# TinySmps.net
KiCad netlist of a schematic drawn in EAGLE
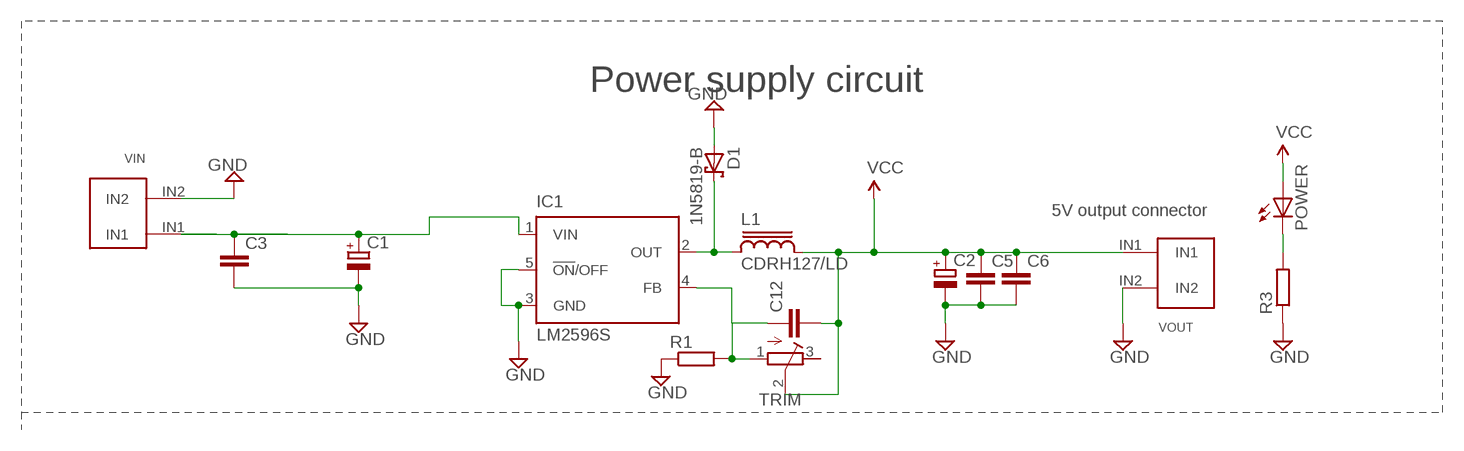
[diagram p0: schematic, sheet 1]

(export (version "E")
  (design (tool "Eeschema 10.0.6"))
  (components
    (comp (ref "C1")
      (value "CPOL-EUE5-10.5")
      (footprint "eagle-import:E5-10,5")
      (libsource (lib "eagle-import") (part "CPOL-EUE5-10.5"))
    )
    (comp (ref "C2")
      (value "CPOL-EUE5-10.5")
      (footprint "eagle-import:E5-10,5")
      (libsource (lib "eagle-import") (part "CPOL-EUE5-10.5"))
    )
    (comp (ref "C3")
      (value "C-EUC1206")
      (footprint "eagle-import:C1206")
      (libsource (lib "eagle-import") (part "C-EUC1206"))
    )
    (comp (ref "C5")
      (value "C-EUC1206")
      (footprint "eagle-import:C1206")
      (libsource (lib "eagle-import") (part "C-EUC1206"))
    )
    (comp (ref "C6")
      (value "C-EUC1206")
      (footprint "eagle-import:C1206")
      (libsource (lib "eagle-import") (part "C-EUC1206"))
    )
    (comp (ref "C12")
      (value "C2,5-3")
      (footprint "eagle-import:C2.5-3")
      (libsource (lib "eagle-import") (part "C2,5-3"))
    )
    (comp (ref "D1")
      (value "1N5819-B")
      (footprint "eagle-import:DO41-7.6")
      (libsource (lib "eagle-import") (part "1N5819-B"))
    )
    (comp (ref "IC1")
      (value "LM2596S")
      (footprint "eagle-import:TO263-5")
      (fields (field (name "MF") "NATIONAL SEMICONDUCTOR") (field (name "MPN") "LM2596S-ADJ/NOPB"))
      (libsource (lib "eagle-import") (part "LM2596S"))
    )
    (comp (ref "L1")
      (value "CDRH127/LD")
      (footprint "eagle-import:CDRH127_LD")
      (libsource (lib "eagle-import") (part "CDRH127/LD"))
    )
    (comp (ref "POWER")
      (value "LEDSML0805")
      (footprint "eagle-import:SML0805")
      (libsource (lib "eagle-import") (part "LEDSML0805"))
    )
    (comp (ref "R1")
      (value "R-EU_0204/7")
      (footprint "eagle-import:0204_7")
      (libsource (lib "eagle-import") (part "R-EU_0204/7"))
    )
    (comp (ref "R3")
      (value "R-EU_R1206")
      (footprint "eagle-import:R1206")
      (libsource (lib "eagle-import") (part "resistor_R-EU_R1206"))
    )
    (comp (ref "TRIM")
      (value "R-TRIMM3296W")
      (footprint "eagle-import:RTRIM3296W")
      (libsource (lib "eagle-import") (part "R-TRIMM3296W"))
    )
    (comp (ref "VIN")
      (value "1X2_5MM")
      (footprint "eagle-import:1X2_5MM")
      (libsource (lib "eagle-import") (part "1X2_5MM"))
    )
    (comp (ref "VOUT")
      (value "1X2_5MM")
      (footprint "eagle-import:1X2_5MM")
      (libsource (lib "eagle-import") (part "1X2_5MM"))
    )
  )
  (nets
    (net (code "1") (name "GND") (class "Default")
      (node (ref "C1") (pin "-") (pinfunction "-_-") (pintype "passive"))
      (node (ref "C2") (pin "-") (pinfunction "-_-") (pintype "passive"))
      (node (ref "C3") (pin "2") (pinfunction "2_2") (pintype "passive"))
      (node (ref "C5") (pin "2") (pinfunction "2_2") (pintype "passive"))
      (node (ref "C6") (pin "2") (pinfunction "2_2") (pintype "passive"))
      (node (ref "D1") (pin "A") (pinfunction "A_A") (pintype "passive"))
      (node (ref "IC1") (pin "3") (pinfunction "GND_3") (pintype "power_in"))
      (node (ref "IC1") (pin "5") (pinfunction "~{ON}/OFF_5") (pintype "input"))
      (node (ref "R1") (pin "1") (pinfunction "1_1") (pintype "passive"))
      (node (ref "R3") (pin "1") (pinfunction "1_1") (pintype "passive"))
      (node (ref "VIN") (pin "IN2") (pinfunction "IN2_IN2") (pintype "bidirectional"))
      (node (ref "VOUT") (pin "IN2") (pinfunction "IN2_IN2") (pintype "bidirectional"))
    )
    (net (code "2") (name "Net-(IC1-FB)") (class "Default")
      (node (ref "C12") (pin "1") (pinfunction "1_1") (pintype "passive"))
      (node (ref "IC1") (pin "4") (pinfunction "FB_4") (pintype "input"))
      (node (ref "R1") (pin "2") (pinfunction "2_2") (pintype "passive"))
      (node (ref "TRIM") (pin "1") (pinfunction "A_1") (pintype "passive"))
    )
    (net (code "3") (name "Net-(IC1-OUT)") (class "Default")
      (node (ref "D1") (pin "C") (pinfunction "C_C") (pintype "passive"))
      (node (ref "IC1") (pin "2") (pinfunction "OUT_2") (pintype "output"))
      (node (ref "L1") (pin "1") (pinfunction "1_1") (pintype "passive"))
    )
    (net (code "4") (name "Net-(IC1-VIN)") (class "Default")
      (node (ref "C1") (pin "+") (pinfunction "+_+") (pintype "passive"))
      (node (ref "C3") (pin "1") (pinfunction "1_1") (pintype "passive"))
      (node (ref "IC1") (pin "1") (pinfunction "VIN_1") (pintype "input"))
      (node (ref "VIN") (pin "IN1") (pinfunction "IN1_IN1") (pintype "bidirectional"))
    )
    (net (code "5") (name "Net-(POWER-PadC)") (class "Default")
      (node (ref "POWER") (pin "C") (pinfunction "C_C") (pintype "passive"))
      (node (ref "R3") (pin "2") (pinfunction "2_2") (pintype "passive"))
    )
    (net (code "6") (name "VCC") (class "Default")
      (node (ref "C12") (pin "2") (pinfunction "2_2") (pintype "passive"))
      (node (ref "C2") (pin "+") (pinfunction "+_+") (pintype "passive"))
      (node (ref "C5") (pin "1") (pinfunction "1_1") (pintype "passive"))
      (node (ref "C6") (pin "1") (pinfunction "1_1") (pintype "passive"))
      (node (ref "L1") (pin "2") (pinfunction "2_2") (pintype "passive"))
      (node (ref "POWER") (pin "A") (pinfunction "A_A") (pintype "passive"))
      (node (ref "TRIM") (pin "2") (pinfunction "S_2") (pintype "passive"))
      (node (ref "VOUT") (pin "IN1") (pinfunction "IN1_IN1") (pintype "bidirectional"))
    )
    (net (code "7") (name "unconnected-(TRIM-E-Pad3)") (class "Default")
      (node (ref "TRIM") (pin "3") (pinfunction "E_3") (pintype "passive"))
    )
  )
)
